# MI0283QT_v12.net
KiCad netlist of a schematic drawn in EAGLE
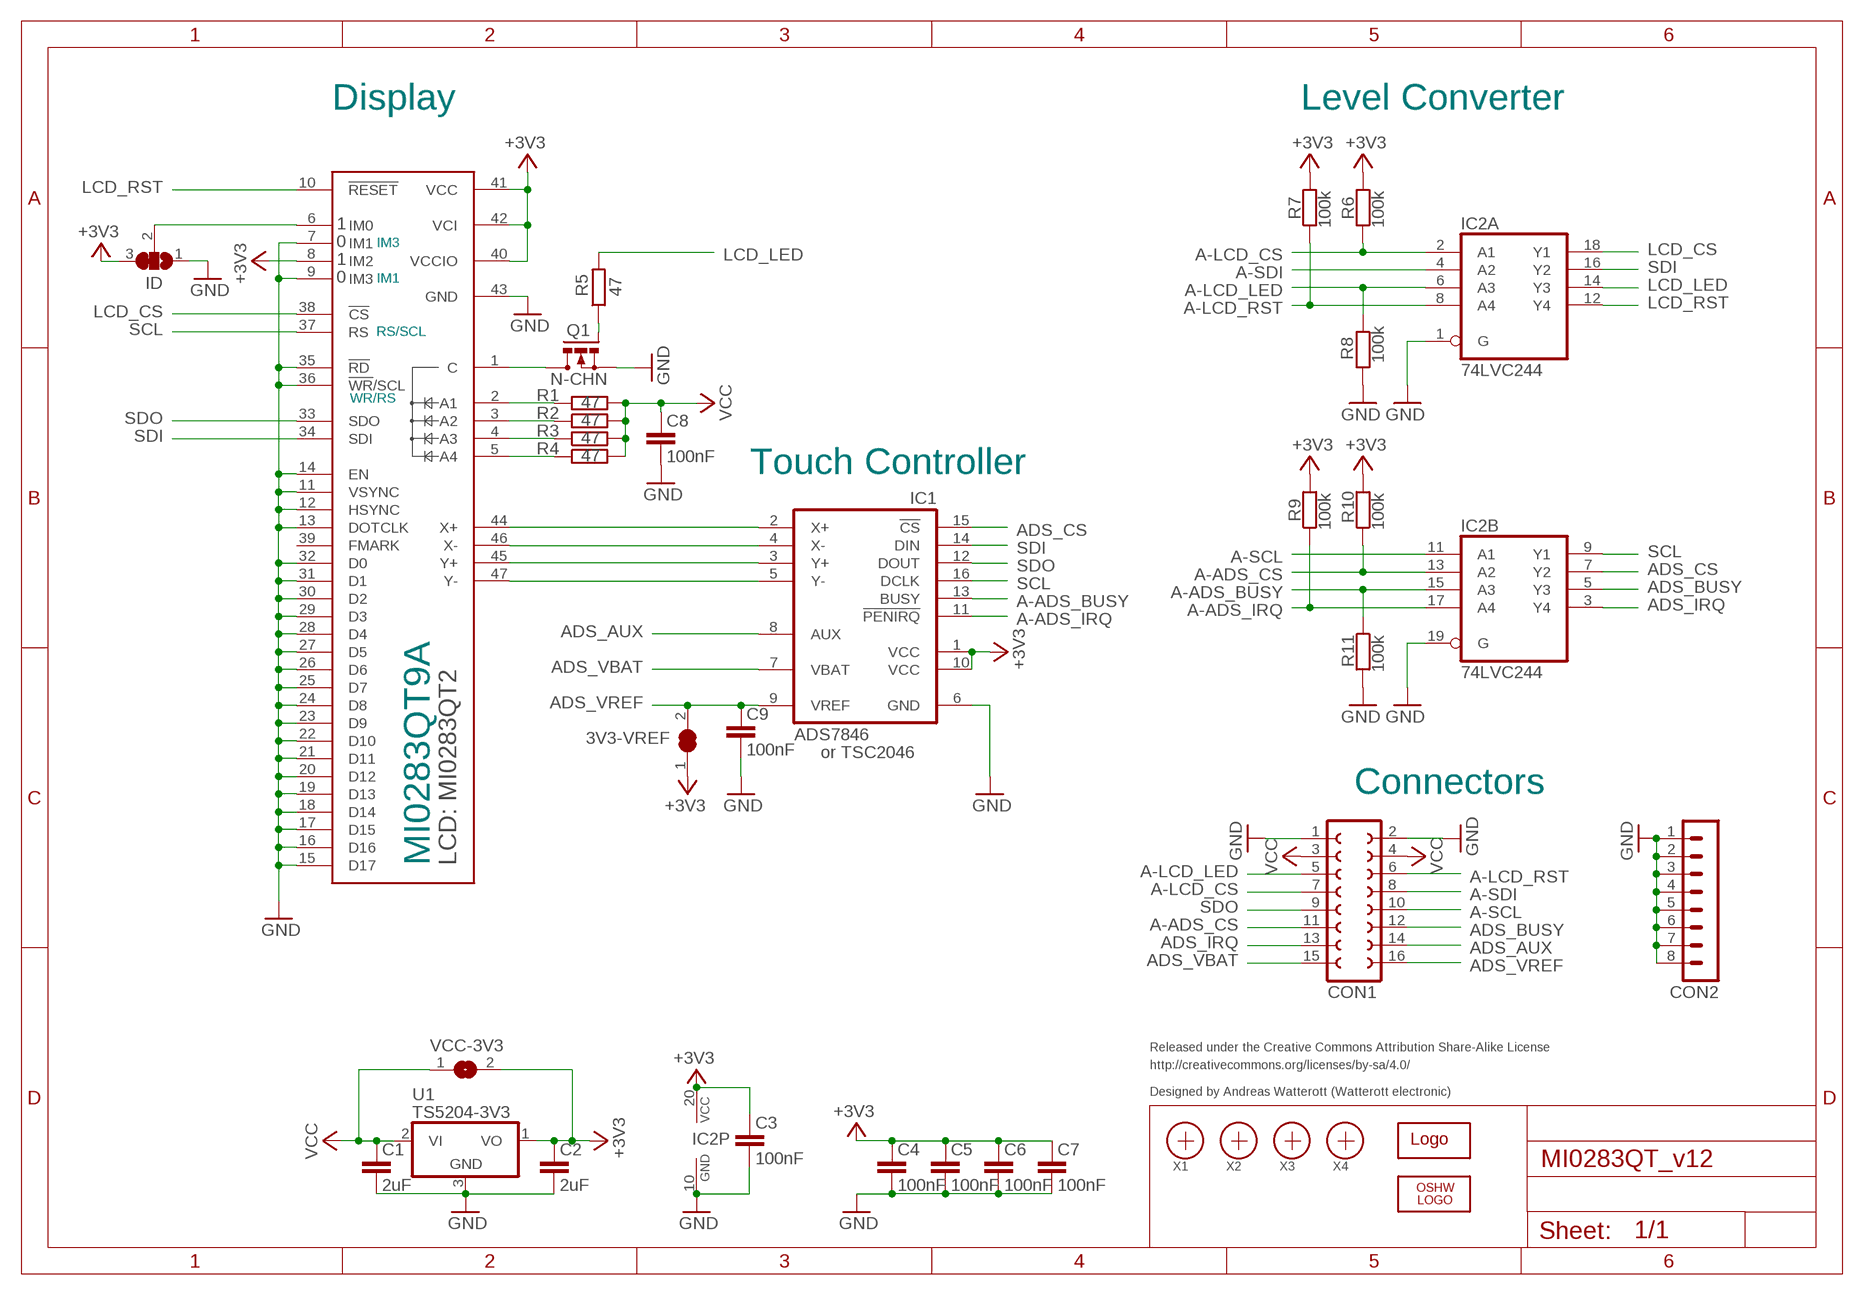
[diagram p0: schematic, sheet 1]

(export (version "E")
  (design (tool "Eeschema 10.0.6"))
  (components
    (comp (ref "3V3-VREF")
      (value "SJ")
      (footprint "eagle-import:SJ")
      (libsource (lib "eagle-import") (part "SJ"))
    )
    (comp (ref "C1")
      (value "2uF")
      (footprint "eagle-import:C0805")
      (libsource (lib "eagle-import") (part "C-EUC0805"))
    )
    (comp (ref "C2")
      (value "2uF")
      (footprint "eagle-import:C0805")
      (libsource (lib "eagle-import") (part "C-EUC0805"))
    )
    (comp (ref "C3")
      (value "100nF")
      (footprint "eagle-import:C0603")
      (libsource (lib "eagle-import") (part "C-EUC0603"))
    )
    (comp (ref "C4")
      (value "100nF")
      (footprint "eagle-import:C0603")
      (libsource (lib "eagle-import") (part "C-EUC0603"))
    )
    (comp (ref "C5")
      (value "100nF")
      (footprint "eagle-import:C0603")
      (libsource (lib "eagle-import") (part "C-EUC0603"))
    )
    (comp (ref "C6")
      (value "100nF")
      (footprint "eagle-import:C0603")
      (libsource (lib "eagle-import") (part "C-EUC0603"))
    )
    (comp (ref "C7")
      (value "100nF")
      (footprint "eagle-import:C0603")
      (libsource (lib "eagle-import") (part "C-EUC0603"))
    )
    (comp (ref "C8")
      (value "100nF")
      (footprint "eagle-import:C0603")
      (libsource (lib "eagle-import") (part "C-EUC0603"))
    )
    (comp (ref "C9")
      (value "100nF")
      (footprint "eagle-import:C0603")
      (libsource (lib "eagle-import") (part "C-EUC0603"))
    )
    (comp (ref "CON1")
      (value "FE08-2")
      (footprint "eagle-import:FE08-2")
      (libsource (lib "eagle-import") (part "FE08-2"))
    )
    (comp (ref "CON2")
      (value "MA08-1")
      (footprint "eagle-import:MA08-1")
      (libsource (lib "eagle-import") (part "MA08-1"))
    )
    (comp (ref "IC1")
      (value "ADS7846")
      (footprint "eagle-import:SSOP16")
      (libsource (lib "eagle-import") (part "ADS7846"))
    )
    (comp (ref "IC2")
      (value "74LVC244")
      (footprint "eagle-import:SO20W")
      (libsource (lib "eagle-import") (part "74244DWHC"))
    )
    (comp (ref "ID")
      (value "SJ2W")
      (footprint "eagle-import:SJ_2")
      (libsource (lib "eagle-import") (part "SJ2W"))
    )
    (comp (ref "LCD")
      (value "MI0283QT")
      (footprint "eagle-import:MI0283QT")
      (libsource (lib "eagle-import") (part "MI0283QT"))
    )
    (comp (ref "LOGO1")
      (value "OSHW_LOGO_6MILX0150-NT")
      (footprint "eagle-import:OSHW_6X150_NOTEXT")
      (libsource (lib "eagle-import") (part "OSHW_LOGO_6MILX0150-NT"))
    )
    (comp (ref "Q1")
      (value "N-CHN")
      (footprint "eagle-import:MICRO3")
      (libsource (lib "eagle-import") (part "IRLML2502"))
    )
    (comp (ref "R1")
      (value "47")
      (footprint "eagle-import:R0603")
      (libsource (lib "eagle-import") (part "R-EU_R0603"))
    )
    (comp (ref "R2")
      (value "47")
      (footprint "eagle-import:R0603")
      (libsource (lib "eagle-import") (part "R-EU_R0603"))
    )
    (comp (ref "R3")
      (value "47")
      (footprint "eagle-import:R0603")
      (libsource (lib "eagle-import") (part "R-EU_R0603"))
    )
    (comp (ref "R4")
      (value "47")
      (footprint "eagle-import:R0603")
      (libsource (lib "eagle-import") (part "R-EU_R0603"))
    )
    (comp (ref "R5")
      (value "47")
      (footprint "eagle-import:R0603")
      (libsource (lib "eagle-import") (part "R-EU_R0603"))
    )
    (comp (ref "R6")
      (value "100k")
      (footprint "eagle-import:R0603")
      (libsource (lib "eagle-import") (part "R-EU_R0603"))
    )
    (comp (ref "R7")
      (value "100k")
      (footprint "eagle-import:R0603")
      (libsource (lib "eagle-import") (part "R-EU_R0603"))
    )
    (comp (ref "R8")
      (value "100k")
      (footprint "eagle-import:R0603")
      (libsource (lib "eagle-import") (part "R-EU_R0603"))
    )
    (comp (ref "R9")
      (value "100k")
      (footprint "eagle-import:R0603")
      (libsource (lib "eagle-import") (part "R-EU_R0603"))
    )
    (comp (ref "R10")
      (value "100k")
      (footprint "eagle-import:R0603")
      (libsource (lib "eagle-import") (part "R-EU_R0603"))
    )
    (comp (ref "R11")
      (value "100k")
      (footprint "eagle-import:R0603")
      (libsource (lib "eagle-import") (part "R-EU_R0603"))
    )
    (comp (ref "U$1")
      (value "WE-LOGO")
      (footprint "eagle-import:WE-LOGO")
      (libsource (lib "eagle-import") (part "WE-LOGO"))
    )
    (comp (ref "U1")
      (value "TS5204-3V3")
      (footprint "eagle-import:SOT23")
      (libsource (lib "eagle-import") (part "TS5204"))
    )
    (comp (ref "VCC-3V3")
      (value "SJ")
      (footprint "eagle-import:SJ")
      (libsource (lib "eagle-import") (part "SJ"))
    )
    (comp (ref "X1")
      (value "PASSER")
      (footprint "eagle-import:PASSER")
      (libsource (lib "eagle-import") (part "PASSER"))
    )
    (comp (ref "X2")
      (value "PASSER")
      (footprint "eagle-import:PASSER")
      (libsource (lib "eagle-import") (part "PASSER"))
    )
    (comp (ref "X3")
      (value "PASSER")
      (footprint "eagle-import:PASSER")
      (libsource (lib "eagle-import") (part "PASSER"))
    )
    (comp (ref "X4")
      (value "PASSER")
      (footprint "eagle-import:PASSER")
      (libsource (lib "eagle-import") (part "PASSER"))
    )
  )
  (nets
    (net (code "1") (name "+3V3") (class "Default")
      (node (ref "3V3-VREF") (pin "1") (pinfunction "1_1") (pintype "passive"))
      (node (ref "C2") (pin "1") (pinfunction "1_1") (pintype "passive"))
      (node (ref "C3") (pin "1") (pinfunction "1_1") (pintype "passive"))
      (node (ref "C4") (pin "1") (pinfunction "1_1") (pintype "passive"))
      (node (ref "C5") (pin "1") (pinfunction "1_1") (pintype "passive"))
      (node (ref "C6") (pin "1") (pinfunction "1_1") (pintype "passive"))
      (node (ref "C7") (pin "1") (pinfunction "1_1") (pintype "passive"))
      (node (ref "IC1") (pin "1") (pinfunction "VCC_1") (pintype "power_in"))
      (node (ref "IC1") (pin "10") (pinfunction "VCC_10") (pintype "power_in"))
      (node (ref "IC2") (pin "20") (pinfunction "VCC_20") (pintype "power_in"))
      (node (ref "ID") (pin "3") (pinfunction "3_3") (pintype "passive"))
      (node (ref "LCD") (pin "40") (pinfunction "VCCIO_40") (pintype "power_in"))
      (node (ref "LCD") (pin "41") (pinfunction "VCC_41") (pintype "power_in"))
      (node (ref "LCD") (pin "42") (pinfunction "VCI_42") (pintype "power_in"))
      (node (ref "LCD") (pin "8") (pinfunction "IM2_8") (pintype "input"))
      (node (ref "R10") (pin "2") (pinfunction "2_2") (pintype "passive"))
      (node (ref "R6") (pin "2") (pinfunction "2_2") (pintype "passive"))
      (node (ref "R7") (pin "2") (pinfunction "2_2") (pintype "passive"))
      (node (ref "R9") (pin "2") (pinfunction "2_2") (pintype "passive"))
      (node (ref "U1") (pin "1") (pinfunction "VO_1") (pintype "passive"))
      (node (ref "VCC-3V3") (pin "2") (pinfunction "2_2") (pintype "passive"))
    )
    (net (code "2") (name "/A-ADS_BUSY") (class "Default")
      (node (ref "IC1") (pin "13") (pinfunction "BUSY_13") (pintype "output"))
      (node (ref "IC2") (pin "15") (pinfunction "A3_15") (pintype "input"))
      (node (ref "R11") (pin "1") (pinfunction "1_1") (pintype "passive"))
    )
    (net (code "3") (name "/A-ADS_CS") (class "Default")
      (node (ref "CON1") (pin "11") (pinfunction "11_11") (pintype "passive"))
      (node (ref "IC2") (pin "13") (pinfunction "A2_13") (pintype "input"))
      (node (ref "R10") (pin "1") (pinfunction "1_1") (pintype "passive"))
    )
    (net (code "4") (name "/A-ADS_IRQ") (class "Default")
      (node (ref "IC1") (pin "11") (pinfunction "~{PENIRQ}_11") (pintype "output"))
      (node (ref "IC2") (pin "17") (pinfunction "A4_17") (pintype "input"))
      (node (ref "R9") (pin "1") (pinfunction "1_1") (pintype "passive"))
    )
    (net (code "5") (name "/A-LCD_CS") (class "Default")
      (node (ref "CON1") (pin "7") (pinfunction "7_7") (pintype "passive"))
      (node (ref "IC2") (pin "2") (pinfunction "A1_2") (pintype "input"))
      (node (ref "R6") (pin "1") (pinfunction "1_1") (pintype "passive"))
    )
    (net (code "6") (name "/A-LCD_LED") (class "Default")
      (node (ref "CON1") (pin "5") (pinfunction "5_5") (pintype "passive"))
      (node (ref "IC2") (pin "6") (pinfunction "A3_6") (pintype "input"))
      (node (ref "R8") (pin "1") (pinfunction "1_1") (pintype "passive"))
    )
    (net (code "7") (name "/A-LCD_RST") (class "Default")
      (node (ref "CON1") (pin "6") (pinfunction "6_6") (pintype "passive"))
      (node (ref "IC2") (pin "8") (pinfunction "A4_8") (pintype "input"))
      (node (ref "R7") (pin "1") (pinfunction "1_1") (pintype "passive"))
    )
    (net (code "8") (name "/A-SCL") (class "Default")
      (node (ref "CON1") (pin "10") (pinfunction "10_10") (pintype "passive"))
      (node (ref "IC2") (pin "11") (pinfunction "A1_11") (pintype "input"))
    )
    (net (code "9") (name "/A-SDI") (class "Default")
      (node (ref "CON1") (pin "8") (pinfunction "8_8") (pintype "passive"))
      (node (ref "IC2") (pin "4") (pinfunction "A2_4") (pintype "input"))
    )
    (net (code "10") (name "/ADS_AUX") (class "Default")
      (node (ref "CON1") (pin "14") (pinfunction "14_14") (pintype "passive"))
      (node (ref "IC1") (pin "8") (pinfunction "AUX_8") (pintype "input"))
    )
    (net (code "11") (name "/ADS_BUSY") (class "Default")
      (node (ref "CON1") (pin "12") (pinfunction "12_12") (pintype "passive"))
      (node (ref "IC2") (pin "5") (pinfunction "Y3_5") (pintype "tri_state"))
    )
    (net (code "12") (name "/ADS_CS") (class "Default")
      (node (ref "IC1") (pin "15") (pinfunction "~{CS}_15") (pintype "input"))
      (node (ref "IC2") (pin "7") (pinfunction "Y2_7") (pintype "tri_state"))
    )
    (net (code "13") (name "/ADS_IRQ") (class "Default")
      (node (ref "CON1") (pin "13") (pinfunction "13_13") (pintype "passive"))
      (node (ref "IC2") (pin "3") (pinfunction "Y4_3") (pintype "tri_state"))
    )
    (net (code "14") (name "/ADS_VBAT") (class "Default")
      (node (ref "CON1") (pin "15") (pinfunction "15_15") (pintype "passive"))
      (node (ref "IC1") (pin "7") (pinfunction "VBAT_7") (pintype "input"))
    )
    (net (code "15") (name "/ADS_VREF") (class "Default")
      (node (ref "3V3-VREF") (pin "2") (pinfunction "2_2") (pintype "passive"))
      (node (ref "C9") (pin "1") (pinfunction "1_1") (pintype "passive"))
      (node (ref "CON1") (pin "16") (pinfunction "16_16") (pintype "passive"))
      (node (ref "IC1") (pin "9") (pinfunction "VREF_9") (pintype "bidirectional"))
    )
    (net (code "16") (name "/LCD_CS") (class "Default")
      (node (ref "IC2") (pin "18") (pinfunction "Y1_18") (pintype "tri_state"))
      (node (ref "LCD") (pin "38") (pinfunction "~{CS}_38") (pintype "input"))
    )
    (net (code "17") (name "/LCD_LED") (class "Default")
      (node (ref "IC2") (pin "14") (pinfunction "Y3_14") (pintype "tri_state"))
      (node (ref "R5") (pin "2") (pinfunction "2_2") (pintype "passive"))
    )
    (net (code "18") (name "/LCD_RST") (class "Default")
      (node (ref "IC2") (pin "12") (pinfunction "Y4_12") (pintype "tri_state"))
      (node (ref "LCD") (pin "10") (pinfunction "~{RESET}_10") (pintype "input"))
    )
    (net (code "19") (name "/SCL") (class "Default")
      (node (ref "IC1") (pin "16") (pinfunction "DCLK_16") (pintype "output"))
      (node (ref "IC2") (pin "9") (pinfunction "Y1_9") (pintype "tri_state"))
      (node (ref "LCD") (pin "37") (pinfunction "RS_37") (pintype "input"))
    )
    (net (code "20") (name "/SDI") (class "Default")
      (node (ref "IC1") (pin "14") (pinfunction "DIN_14") (pintype "input"))
      (node (ref "IC2") (pin "16") (pinfunction "Y2_16") (pintype "tri_state"))
      (node (ref "LCD") (pin "34") (pinfunction "SDI_34") (pintype "input"))
    )
    (net (code "21") (name "/SDO") (class "Default")
      (node (ref "CON1") (pin "9") (pinfunction "9_9") (pintype "passive"))
      (node (ref "IC1") (pin "12") (pinfunction "DOUT_12") (pintype "input"))
      (node (ref "LCD") (pin "33") (pinfunction "SDO_33") (pintype "output"))
    )
    (net (code "22") (name "GND") (class "Default")
      (node (ref "C1") (pin "2") (pinfunction "2_2") (pintype "passive"))
      (node (ref "C2") (pin "2") (pinfunction "2_2") (pintype "passive"))
      (node (ref "C3") (pin "2") (pinfunction "2_2") (pintype "passive"))
      (node (ref "C4") (pin "2") (pinfunction "2_2") (pintype "passive"))
      (node (ref "C5") (pin "2") (pinfunction "2_2") (pintype "passive"))
      (node (ref "C6") (pin "2") (pinfunction "2_2") (pintype "passive"))
      (node (ref "C7") (pin "2") (pinfunction "2_2") (pintype "passive"))
      (node (ref "C8") (pin "2") (pinfunction "2_2") (pintype "passive"))
      (node (ref "C9") (pin "2") (pinfunction "2_2") (pintype "passive"))
      (node (ref "CON1") (pin "1") (pinfunction "1_1") (pintype "passive"))
      (node (ref "CON1") (pin "2") (pinfunction "2_2") (pintype "passive"))
      (node (ref "CON2") (pin "1") (pinfunction "1_1") (pintype "passive"))
      (node (ref "CON2") (pin "2") (pinfunction "2_2") (pintype "passive"))
      (node (ref "CON2") (pin "3") (pinfunction "3_3") (pintype "passive"))
      (node (ref "CON2") (pin "4") (pinfunction "4_4") (pintype "passive"))
      (node (ref "CON2") (pin "5") (pinfunction "5_5") (pintype "passive"))
      (node (ref "CON2") (pin "6") (pinfunction "6_6") (pintype "passive"))
      (node (ref "CON2") (pin "7") (pinfunction "7_7") (pintype "passive"))
      (node (ref "CON2") (pin "8") (pinfunction "8_8") (pintype "passive"))
      (node (ref "IC1") (pin "6") (pinfunction "GND_6") (pintype "power_in"))
      (node (ref "IC2") (pin "1") (pinfunction "G_1") (pintype "input"))
      (node (ref "IC2") (pin "10") (pinfunction "GND_10") (pintype "power_in"))
      (node (ref "IC2") (pin "19") (pinfunction "G_19") (pintype "input"))
      (node (ref "ID") (pin "1") (pinfunction "1_1") (pintype "passive"))
      (node (ref "LCD") (pin "11") (pinfunction "VSYNC_11") (pintype "input"))
      (node (ref "LCD") (pin "12") (pinfunction "HSYNC_12") (pintype "input"))
      (node (ref "LCD") (pin "13") (pinfunction "DOTCLK_13") (pintype "input"))
      (node (ref "LCD") (pin "14") (pinfunction "EN_14") (pintype "input"))
      (node (ref "LCD") (pin "15") (pinfunction "D17_15") (pintype "input"))
      (node (ref "LCD") (pin "16") (pinfunction "D16_16") (pintype "input"))
      (node (ref "LCD") (pin "17") (pinfunction "D15_17") (pintype "input"))
      (node (ref "LCD") (pin "18") (pinfunction "D14_18") (pintype "input"))
      (node (ref "LCD") (pin "19") (pinfunction "D13_19") (pintype "input"))
      (node (ref "LCD") (pin "20") (pinfunction "D12_20") (pintype "input"))
      (node (ref "LCD") (pin "21") (pinfunction "D11_21") (pintype "input"))
      (node (ref "LCD") (pin "22") (pinfunction "D10_22") (pintype "input"))
      (node (ref "LCD") (pin "23") (pinfunction "D9_23") (pintype "input"))
      (node (ref "LCD") (pin "24") (pinfunction "D8_24") (pintype "input"))
      (node (ref "LCD") (pin "25") (pinfunction "D7_25") (pintype "input"))
      (node (ref "LCD") (pin "26") (pinfunction "D6_26") (pintype "input"))
      (node (ref "LCD") (pin "27") (pinfunction "D5_27") (pintype "input"))
      (node (ref "LCD") (pin "28") (pinfunction "D4_28") (pintype "input"))
      (node (ref "LCD") (pin "29") (pinfunction "D3_29") (pintype "input"))
      (node (ref "LCD") (pin "30") (pinfunction "D2_30") (pintype "input"))
      (node (ref "LCD") (pin "31") (pinfunction "D1_31") (pintype "input"))
      (node (ref "LCD") (pin "32") (pinfunction "D0_32") (pintype "input"))
      (node (ref "LCD") (pin "35") (pinfunction "~{RD}_35") (pintype "input"))
      (node (ref "LCD") (pin "36") (pinfunction "~{WR}/SCL_36") (pintype "input"))
      (node (ref "LCD") (pin "43") (pinfunction "GND_43") (pintype "power_in"))
      (node (ref "LCD") (pin "7") (pinfunction "IM1_7") (pintype "input"))
      (node (ref "LCD") (pin "9") (pinfunction "IM3_9") (pintype "input"))
      (node (ref "Q1") (pin "2") (pinfunction "S_2") (pintype "passive"))
      (node (ref "R11") (pin "2") (pinfunction "2_2") (pintype "passive"))
      (node (ref "R8") (pin "2") (pinfunction "2_2") (pintype "passive"))
      (node (ref "U1") (pin "3") (pinfunction "GND_3") (pintype "passive"))
    )
    (net (code "23") (name "Net-(IC1-X+)") (class "Default")
      (node (ref "IC1") (pin "2") (pinfunction "X+_2") (pintype "input"))
      (node (ref "LCD") (pin "44") (pinfunction "X+_44") (pintype "passive"))
    )
    (net (code "24") (name "Net-(IC1-X-)") (class "Default")
      (node (ref "IC1") (pin "4") (pinfunction "X-_4") (pintype "input"))
      (node (ref "LCD") (pin "46") (pinfunction "X-_46") (pintype "passive"))
    )
    (net (code "25") (name "Net-(IC1-Y+)") (class "Default")
      (node (ref "IC1") (pin "3") (pinfunction "Y+_3") (pintype "input"))
      (node (ref "LCD") (pin "45") (pinfunction "Y+_45") (pintype "passive"))
    )
    (net (code "26") (name "Net-(IC1-Y-)") (class "Default")
      (node (ref "IC1") (pin "5") (pinfunction "Y-_5") (pintype "input"))
      (node (ref "LCD") (pin "47") (pinfunction "Y-_47") (pintype "passive"))
    )
    (net (code "27") (name "Net-(LCD-A1)") (class "Default")
      (node (ref "LCD") (pin "2") (pinfunction "A1_2") (pintype "power_in"))
      (node (ref "R1") (pin "1") (pinfunction "1_1") (pintype "passive"))
    )
    (net (code "28") (name "Net-(LCD-A2)") (class "Default")
      (node (ref "LCD") (pin "3") (pinfunction "A2_3") (pintype "power_in"))
      (node (ref "R2") (pin "1") (pinfunction "1_1") (pintype "passive"))
    )
    (net (code "29") (name "Net-(LCD-A3)") (class "Default")
      (node (ref "LCD") (pin "4") (pinfunction "A3_4") (pintype "power_in"))
      (node (ref "R3") (pin "1") (pinfunction "1_1") (pintype "passive"))
    )
    (net (code "30") (name "Net-(LCD-A4)") (class "Default")
      (node (ref "LCD") (pin "5") (pinfunction "A4_5") (pintype "power_in"))
      (node (ref "R4") (pin "1") (pinfunction "1_1") (pintype "passive"))
    )
    (net (code "31") (name "Net-(LCD-C)") (class "Default")
      (node (ref "LCD") (pin "1") (pinfunction "C_1") (pintype "power_in"))
      (node (ref "Q1") (pin "3") (pinfunction "D_3") (pintype "passive"))
    )
    (net (code "32") (name "Net-(LCD-IM0)") (class "Default")
      (node (ref "ID") (pin "2") (pinfunction "2_2") (pintype "passive"))
      (node (ref "LCD") (pin "6") (pinfunction "IM0_6") (pintype "input"))
    )
    (net (code "33") (name "Net-(Q1-G)") (class "Default")
      (node (ref "Q1") (pin "1") (pinfunction "G_1") (pintype "passive"))
      (node (ref "R5") (pin "1") (pinfunction "1_1") (pintype "passive"))
    )
    (net (code "34") (name "VCC") (class "Default")
      (node (ref "C1") (pin "1") (pinfunction "1_1") (pintype "passive"))
      (node (ref "C8") (pin "1") (pinfunction "1_1") (pintype "passive"))
      (node (ref "CON1") (pin "3") (pinfunction "3_3") (pintype "passive"))
      (node (ref "CON1") (pin "4") (pinfunction "4_4") (pintype "passive"))
      (node (ref "R1") (pin "2") (pinfunction "2_2") (pintype "passive"))
      (node (ref "R2") (pin "2") (pinfunction "2_2") (pintype "passive"))
      (node (ref "R3") (pin "2") (pinfunction "2_2") (pintype "passive"))
      (node (ref "R4") (pin "2") (pinfunction "2_2") (pintype "passive"))
      (node (ref "U1") (pin "2") (pinfunction "VI_2") (pintype "input"))
      (node (ref "VCC-3V3") (pin "1") (pinfunction "1_1") (pintype "passive"))
    )
    (net (code "35") (name "unconnected-(LCD-FMARK-Pad39)") (class "Default")
      (node (ref "LCD") (pin "39") (pinfunction "FMARK_39") (pintype "output"))
    )
  )
)
